# CubeX2000.net
KiCad netlist of a schematic drawn in EAGLE
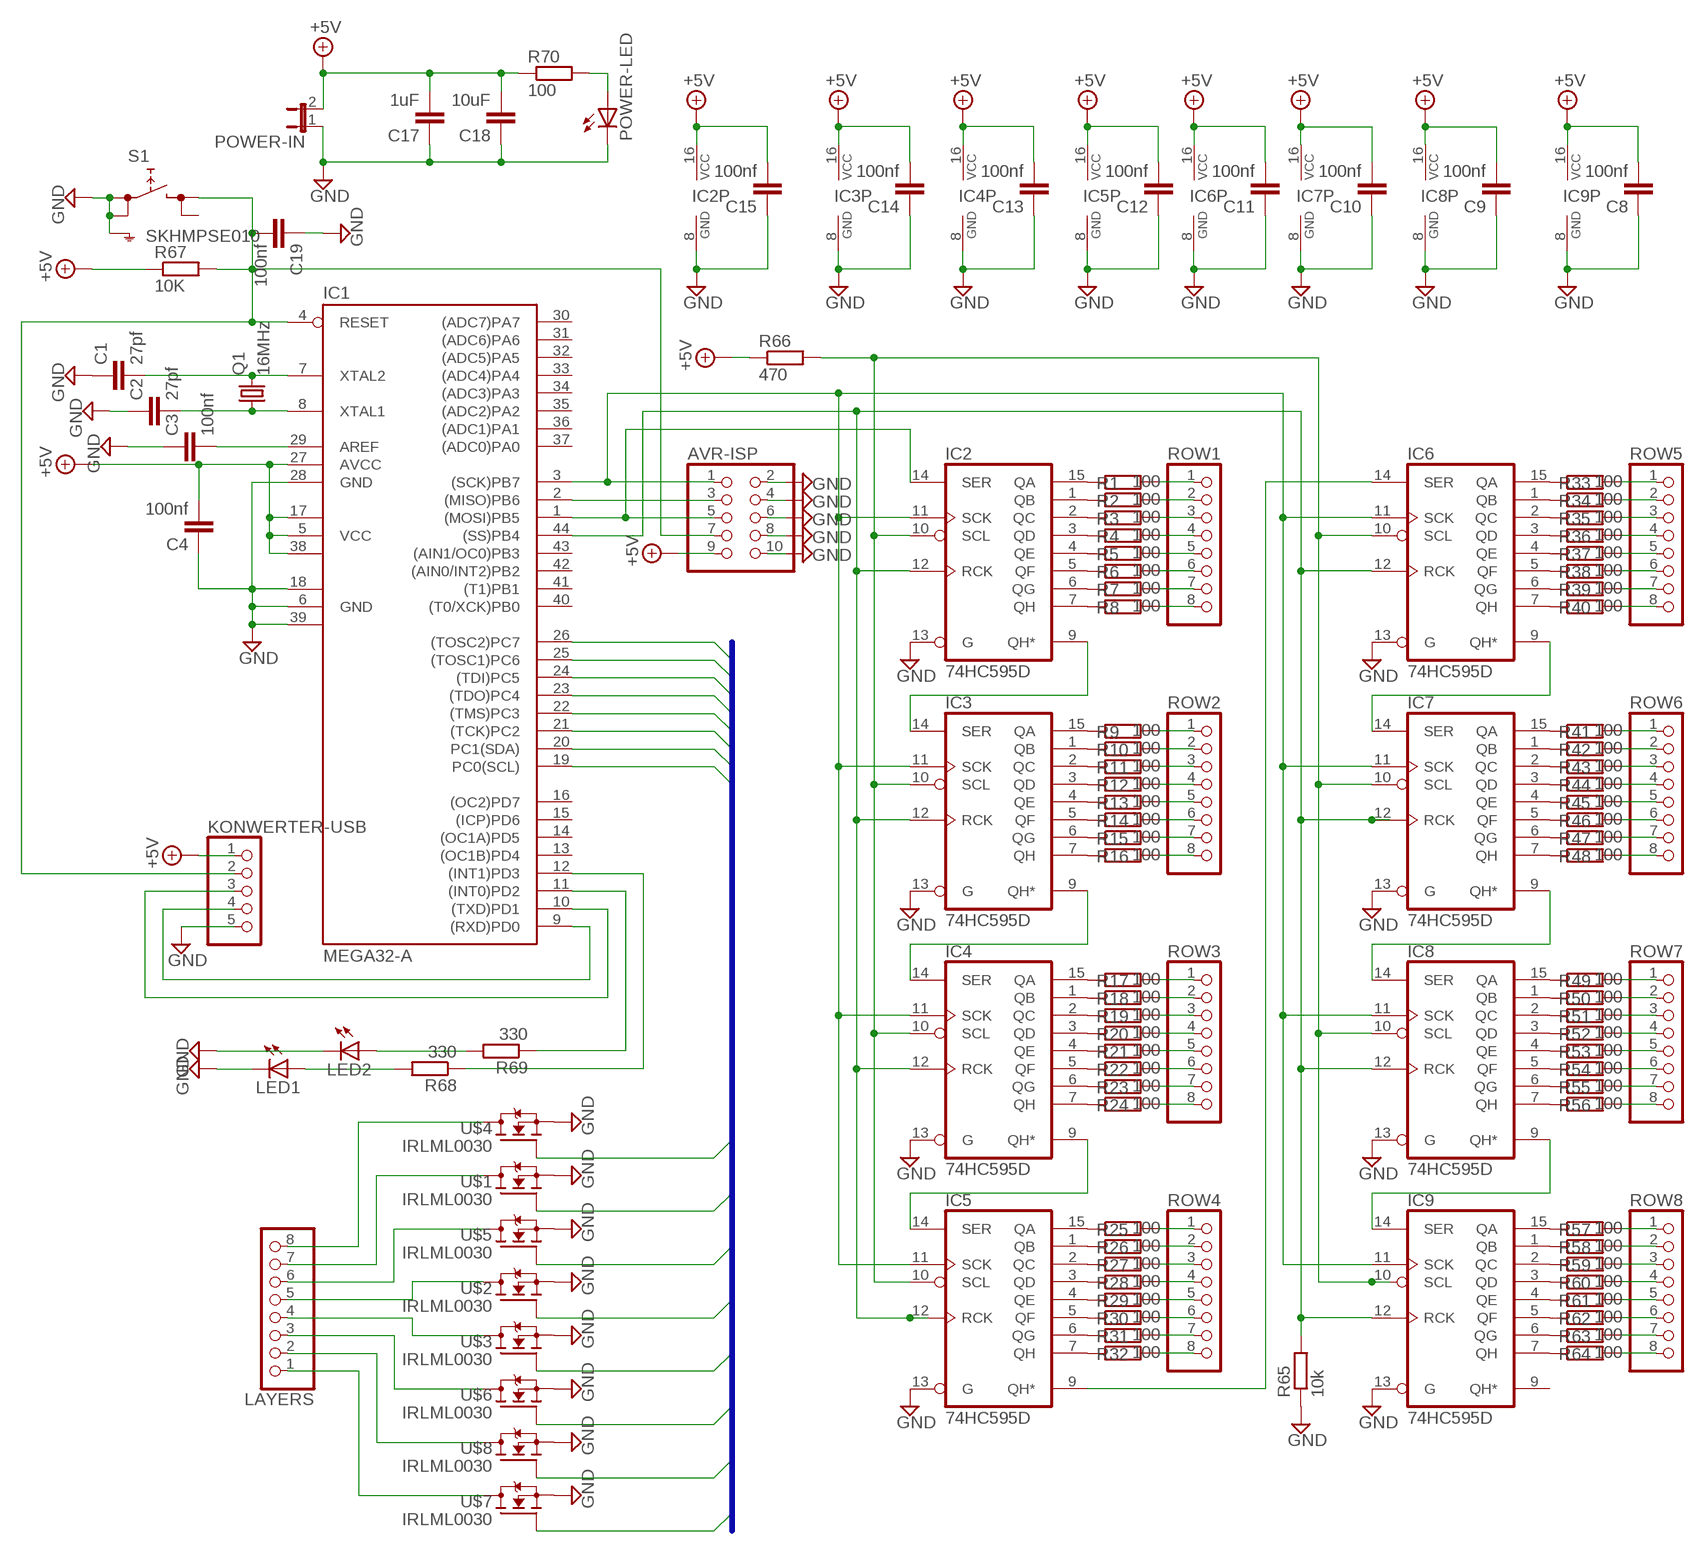
[diagram p0: schematic, sheet 1]

(export (version "E")
  (design (tool "Eeschema 10.0.6"))
  (components
    (comp (ref "AVR-ISP")
      (value "PINHD-2X5")
      (footprint "eagle-import:2X05")
      (libsource (lib "eagle-import") (part "PINHD-2X5"))
    )
    (comp (ref "C1")
      (value "27pf")
      (footprint "eagle-import:C1206")
      (libsource (lib "eagle-import") (part "C-EUC1206"))
    )
    (comp (ref "C2")
      (value "27pf")
      (footprint "eagle-import:C1206")
      (libsource (lib "eagle-import") (part "C-EUC1206"))
    )
    (comp (ref "C3")
      (value "100nf")
      (footprint "eagle-import:C1206")
      (libsource (lib "eagle-import") (part "C-EUC1206"))
    )
    (comp (ref "C4")
      (value "100nf")
      (footprint "eagle-import:C1206")
      (libsource (lib "eagle-import") (part "C-EUC1206"))
    )
    (comp (ref "C8")
      (value "100nf")
      (footprint "eagle-import:C1206")
      (libsource (lib "eagle-import") (part "C-EUC1206"))
    )
    (comp (ref "C9")
      (value "100nf")
      (footprint "eagle-import:C1206")
      (libsource (lib "eagle-import") (part "C-EUC1206"))
    )
    (comp (ref "C10")
      (value "100nf")
      (footprint "eagle-import:C1206")
      (libsource (lib "eagle-import") (part "C-EUC1206"))
    )
    (comp (ref "C11")
      (value "100nf")
      (footprint "eagle-import:C1206")
      (libsource (lib "eagle-import") (part "C-EUC1206"))
    )
    (comp (ref "C12")
      (value "100nf")
      (footprint "eagle-import:C1206")
      (libsource (lib "eagle-import") (part "C-EUC1206"))
    )
    (comp (ref "C13")
      (value "100nf")
      (footprint "eagle-import:C1206")
      (libsource (lib "eagle-import") (part "C-EUC1206"))
    )
    (comp (ref "C14")
      (value "100nf")
      (footprint "eagle-import:C1206")
      (libsource (lib "eagle-import") (part "C-EUC1206"))
    )
    (comp (ref "C15")
      (value "100nf")
      (footprint "eagle-import:C1206")
      (libsource (lib "eagle-import") (part "C-EUC1206"))
    )
    (comp (ref "C17")
      (value "1uF")
      (footprint "eagle-import:C1206")
      (libsource (lib "eagle-import") (part "C-EUC1206"))
    )
    (comp (ref "C18")
      (value "10uF")
      (footprint "eagle-import:C1206")
      (libsource (lib "eagle-import") (part "C-EUC1206"))
    )
    (comp (ref "C19")
      (value "100nf")
      (footprint "eagle-import:C1206")
      (libsource (lib "eagle-import") (part "C-EUC1206"))
    )
    (comp (ref "IC1")
      (value "MEGA32-A")
      (footprint "eagle-import:TQFP44")
      (fields (field (name "MPN") "ATMEGA32-16AU"))
      (libsource (lib "eagle-import") (part "MEGA32-A"))
    )
    (comp (ref "IC2")
      (value "74HC595D")
      (footprint "eagle-import:SO16")
      (libsource (lib "eagle-import") (part "74595DHC"))
    )
    (comp (ref "IC3")
      (value "74HC595D")
      (footprint "eagle-import:SO16")
      (libsource (lib "eagle-import") (part "74595DHC"))
    )
    (comp (ref "IC4")
      (value "74HC595D")
      (footprint "eagle-import:SO16")
      (libsource (lib "eagle-import") (part "74595DHC"))
    )
    (comp (ref "IC5")
      (value "74HC595D")
      (footprint "eagle-import:SO16")
      (libsource (lib "eagle-import") (part "74595DHC"))
    )
    (comp (ref "IC6")
      (value "74HC595D")
      (footprint "eagle-import:SO16")
      (libsource (lib "eagle-import") (part "74595DHC"))
    )
    (comp (ref "IC7")
      (value "74HC595D")
      (footprint "eagle-import:SO16")
      (libsource (lib "eagle-import") (part "74595DHC"))
    )
    (comp (ref "IC8")
      (value "74HC595D")
      (footprint "eagle-import:SO16")
      (libsource (lib "eagle-import") (part "74595DHC"))
    )
    (comp (ref "IC9")
      (value "74HC595D")
      (footprint "eagle-import:SO16")
      (libsource (lib "eagle-import") (part "74595DHC"))
    )
    (comp (ref "KONWERTER-USB")
      (value "PINHD-1X5")
      (footprint "eagle-import:1X05")
      (libsource (lib "eagle-import") (part "PINHD-1X5"))
    )
    (comp (ref "LAYERS")
      (value "PINHD-1X8")
      (footprint "eagle-import:1X08")
      (libsource (lib "eagle-import") (part "PINHD-1X8"))
    )
    (comp (ref "LED1")
      (value "LEDSMT1206")
      (footprint "eagle-import:1206")
      (libsource (lib "eagle-import") (part "LEDSMT1206"))
    )
    (comp (ref "LED2")
      (value "LEDSMT1206")
      (footprint "eagle-import:1206")
      (libsource (lib "eagle-import") (part "LEDSMT1206"))
    )
    (comp (ref "POWER-IN")
      (value "JP1E")
      (footprint "eagle-import:JP1")
      (libsource (lib "eagle-import") (part "JP1E"))
    )
    (comp (ref "POWER-LED")
      (value "LEDSMT1206")
      (footprint "eagle-import:1206")
      (libsource (lib "eagle-import") (part "LEDSMT1206"))
    )
    (comp (ref "Q1")
      (value "16MHz")
      (footprint "eagle-import:HC49_S")
      (libsource (lib "eagle-import") (part "CRYSTALHC49S"))
    )
    (comp (ref "R1")
      (value "100")
      (footprint "eagle-import:R1206")
      (libsource (lib "eagle-import") (part "R-EU_R1206"))
    )
    (comp (ref "R2")
      (value "100")
      (footprint "eagle-import:R1206")
      (libsource (lib "eagle-import") (part "R-EU_R1206"))
    )
    (comp (ref "R3")
      (value "100")
      (footprint "eagle-import:R1206")
      (libsource (lib "eagle-import") (part "R-EU_R1206"))
    )
    (comp (ref "R4")
      (value "100")
      (footprint "eagle-import:R1206")
      (libsource (lib "eagle-import") (part "R-EU_R1206"))
    )
    (comp (ref "R5")
      (value "100")
      (footprint "eagle-import:R1206")
      (libsource (lib "eagle-import") (part "R-EU_R1206"))
    )
    (comp (ref "R6")
      (value "100")
      (footprint "eagle-import:R1206")
      (libsource (lib "eagle-import") (part "R-EU_R1206"))
    )
    (comp (ref "R7")
      (value "100")
      (footprint "eagle-import:R1206")
      (libsource (lib "eagle-import") (part "R-EU_R1206"))
    )
    (comp (ref "R8")
      (value "100")
      (footprint "eagle-import:R1206")
      (libsource (lib "eagle-import") (part "R-EU_R1206"))
    )
    (comp (ref "R9")
      (value "100")
      (footprint "eagle-import:R1206")
      (libsource (lib "eagle-import") (part "R-EU_R1206"))
    )
    (comp (ref "R10")
      (value "100")
      (footprint "eagle-import:R1206")
      (libsource (lib "eagle-import") (part "R-EU_R1206"))
    )
    (comp (ref "R11")
      (value "100")
      (footprint "eagle-import:R1206")
      (libsource (lib "eagle-import") (part "R-EU_R1206"))
    )
    (comp (ref "R12")
      (value "100")
      (footprint "eagle-import:R1206")
      (libsource (lib "eagle-import") (part "R-EU_R1206"))
    )
    (comp (ref "R13")
      (value "100")
      (footprint "eagle-import:R1206")
      (libsource (lib "eagle-import") (part "R-EU_R1206"))
    )
    (comp (ref "R14")
      (value "100")
      (footprint "eagle-import:R1206")
      (libsource (lib "eagle-import") (part "R-EU_R1206"))
    )
    (comp (ref "R15")
      (value "100")
      (footprint "eagle-import:R1206")
      (libsource (lib "eagle-import") (part "R-EU_R1206"))
    )
    (comp (ref "R16")
      (value "100")
      (footprint "eagle-import:R1206")
      (libsource (lib "eagle-import") (part "R-EU_R1206"))
    )
    (comp (ref "R17")
      (value "100")
      (footprint "eagle-import:R1206")
      (libsource (lib "eagle-import") (part "R-EU_R1206"))
    )
    (comp (ref "R18")
      (value "100")
      (footprint "eagle-import:R1206")
      (libsource (lib "eagle-import") (part "R-EU_R1206"))
    )
    (comp (ref "R19")
      (value "100")
      (footprint "eagle-import:R1206")
      (libsource (lib "eagle-import") (part "R-EU_R1206"))
    )
    (comp (ref "R20")
      (value "100")
      (footprint "eagle-import:R1206")
      (libsource (lib "eagle-import") (part "R-EU_R1206"))
    )
    (comp (ref "R21")
      (value "100")
      (footprint "eagle-import:R1206")
      (libsource (lib "eagle-import") (part "R-EU_R1206"))
    )
    (comp (ref "R22")
      (value "100")
      (footprint "eagle-import:R1206")
      (libsource (lib "eagle-import") (part "R-EU_R1206"))
    )
    (comp (ref "R23")
      (value "100")
      (footprint "eagle-import:R1206")
      (libsource (lib "eagle-import") (part "R-EU_R1206"))
    )
    (comp (ref "R24")
      (value "100")
      (footprint "eagle-import:R1206")
      (libsource (lib "eagle-import") (part "R-EU_R1206"))
    )
    (comp (ref "R25")
      (value "100")
      (footprint "eagle-import:R1206")
      (libsource (lib "eagle-import") (part "R-EU_R1206"))
    )
    (comp (ref "R26")
      (value "100")
      (footprint "eagle-import:R1206")
      (libsource (lib "eagle-import") (part "R-EU_R1206"))
    )
    (comp (ref "R27")
      (value "100")
      (footprint "eagle-import:R1206")
      (libsource (lib "eagle-import") (part "R-EU_R1206"))
    )
    (comp (ref "R28")
      (value "100")
      (footprint "eagle-import:R1206")
      (libsource (lib "eagle-import") (part "R-EU_R1206"))
    )
    (comp (ref "R29")
      (value "100")
      (footprint "eagle-import:R1206")
      (libsource (lib "eagle-import") (part "R-EU_R1206"))
    )
    (comp (ref "R30")
      (value "100")
      (footprint "eagle-import:R1206")
      (libsource (lib "eagle-import") (part "R-EU_R1206"))
    )
    (comp (ref "R31")
      (value "100")
      (footprint "eagle-import:R1206")
      (libsource (lib "eagle-import") (part "R-EU_R1206"))
    )
    (comp (ref "R32")
      (value "100")
      (footprint "eagle-import:R1206")
      (libsource (lib "eagle-import") (part "R-EU_R1206"))
    )
    (comp (ref "R33")
      (value "100")
      (footprint "eagle-import:R1206")
      (libsource (lib "eagle-import") (part "R-EU_R1206"))
    )
    (comp (ref "R34")
      (value "100")
      (footprint "eagle-import:R1206")
      (libsource (lib "eagle-import") (part "R-EU_R1206"))
    )
    (comp (ref "R35")
      (value "100")
      (footprint "eagle-import:R1206")
      (libsource (lib "eagle-import") (part "R-EU_R1206"))
    )
    (comp (ref "R36")
      (value "100")
      (footprint "eagle-import:R1206")
      (libsource (lib "eagle-import") (part "R-EU_R1206"))
    )
    (comp (ref "R37")
      (value "100")
      (footprint "eagle-import:R1206")
      (libsource (lib "eagle-import") (part "R-EU_R1206"))
    )
    (comp (ref "R38")
      (value "100")
      (footprint "eagle-import:R1206")
      (libsource (lib "eagle-import") (part "R-EU_R1206"))
    )
    (comp (ref "R39")
      (value "100")
      (footprint "eagle-import:R1206")
      (libsource (lib "eagle-import") (part "R-EU_R1206"))
    )
    (comp (ref "R40")
      (value "100")
      (footprint "eagle-import:R1206")
      (libsource (lib "eagle-import") (part "R-EU_R1206"))
    )
    (comp (ref "R41")
      (value "100")
      (footprint "eagle-import:R1206")
      (libsource (lib "eagle-import") (part "R-EU_R1206"))
    )
    (comp (ref "R42")
      (value "100")
      (footprint "eagle-import:R1206")
      (libsource (lib "eagle-import") (part "R-EU_R1206"))
    )
    (comp (ref "R43")
      (value "100")
      (footprint "eagle-import:R1206")
      (libsource (lib "eagle-import") (part "R-EU_R1206"))
    )
    (comp (ref "R44")
      (value "100")
      (footprint "eagle-import:R1206")
      (libsource (lib "eagle-import") (part "R-EU_R1206"))
    )
    (comp (ref "R45")
      (value "100")
      (footprint "eagle-import:R1206")
      (libsource (lib "eagle-import") (part "R-EU_R1206"))
    )
    (comp (ref "R46")
      (value "100")
      (footprint "eagle-import:R1206")
      (libsource (lib "eagle-import") (part "R-EU_R1206"))
    )
    (comp (ref "R47")
      (value "100")
      (footprint "eagle-import:R1206")
      (libsource (lib "eagle-import") (part "R-EU_R1206"))
    )
    (comp (ref "R48")
      (value "100")
      (footprint "eagle-import:R1206")
      (libsource (lib "eagle-import") (part "R-EU_R1206"))
    )
    (comp (ref "R49")
      (value "100")
      (footprint "eagle-import:R1206")
      (libsource (lib "eagle-import") (part "R-EU_R1206"))
    )
    (comp (ref "R50")
      (value "100")
      (footprint "eagle-import:R1206")
      (libsource (lib "eagle-import") (part "R-EU_R1206"))
    )
    (comp (ref "R51")
      (value "100")
      (footprint "eagle-import:R1206")
      (libsource (lib "eagle-import") (part "R-EU_R1206"))
    )
    (comp (ref "R52")
      (value "100")
      (footprint "eagle-import:R1206")
      (libsource (lib "eagle-import") (part "R-EU_R1206"))
    )
    (comp (ref "R53")
      (value "100")
      (footprint "eagle-import:R1206")
      (libsource (lib "eagle-import") (part "R-EU_R1206"))
    )
    (comp (ref "R54")
      (value "100")
      (footprint "eagle-import:R1206")
      (libsource (lib "eagle-import") (part "R-EU_R1206"))
    )
    (comp (ref "R55")
      (value "100")
      (footprint "eagle-import:R1206")
      (libsource (lib "eagle-import") (part "R-EU_R1206"))
    )
    (comp (ref "R56")
      (value "100")
      (footprint "eagle-import:R1206")
      (libsource (lib "eagle-import") (part "R-EU_R1206"))
    )
    (comp (ref "R57")
      (value "100")
      (footprint "eagle-import:R1206")
      (libsource (lib "eagle-import") (part "R-EU_R1206"))
    )
    (comp (ref "R58")
      (value "100")
      (footprint "eagle-import:R1206")
      (libsource (lib "eagle-import") (part "R-EU_R1206"))
    )
    (comp (ref "R59")
      (value "100")
      (footprint "eagle-import:R1206")
      (libsource (lib "eagle-import") (part "R-EU_R1206"))
    )
    (comp (ref "R60")
      (value "100")
      (footprint "eagle-import:R1206")
      (libsource (lib "eagle-import") (part "R-EU_R1206"))
    )
    (comp (ref "R61")
      (value "100")
      (footprint "eagle-import:R1206")
      (libsource (lib "eagle-import") (part "R-EU_R1206"))
    )
    (comp (ref "R62")
      (value "100")
      (footprint "eagle-import:R1206")
      (libsource (lib "eagle-import") (part "R-EU_R1206"))
    )
    (comp (ref "R63")
      (value "100")
      (footprint "eagle-import:R1206")
      (libsource (lib "eagle-import") (part "R-EU_R1206"))
    )
    (comp (ref "R64")
      (value "100")
      (footprint "eagle-import:R1206")
      (libsource (lib "eagle-import") (part "R-EU_R1206"))
    )
    (comp (ref "R65")
      (value "10k")
      (footprint "eagle-import:R1206")
      (libsource (lib "eagle-import") (part "R-EU_R1206"))
    )
    (comp (ref "R66")
      (value "470")
      (footprint "eagle-import:R1206")
      (libsource (lib "eagle-import") (part "R-EU_R1206"))
    )
    (comp (ref "R67")
      (value "10K")
      (footprint "eagle-import:R1206")
      (libsource (lib "eagle-import") (part "R-EU_R1206"))
    )
    (comp (ref "R68")
      (value "330")
      (footprint "eagle-import:R1206")
      (libsource (lib "eagle-import") (part "R-EU_R1206"))
    )
    (comp (ref "R69")
      (value "330")
      (footprint "eagle-import:R1206")
      (libsource (lib "eagle-import") (part "R-EU_R1206"))
    )
    (comp (ref "R70")
      (value "100")
      (footprint "eagle-import:R1206")
      (libsource (lib "eagle-import") (part "R-EU_R1206"))
    )
    (comp (ref "ROW1")
      (value "PINHD-1X8")
      (footprint "eagle-import:1X08")
      (libsource (lib "eagle-import") (part "PINHD-1X8"))
    )
    (comp (ref "ROW2")
      (value "PINHD-1X8")
      (footprint "eagle-import:1X08")
      (libsource (lib "eagle-import") (part "PINHD-1X8"))
    )
    (comp (ref "ROW3")
      (value "PINHD-1X8")
      (footprint "eagle-import:1X08")
      (libsource (lib "eagle-import") (part "PINHD-1X8"))
    )
    (comp (ref "ROW4")
      (value "PINHD-1X8")
      (footprint "eagle-import:1X08")
      (libsource (lib "eagle-import") (part "PINHD-1X8"))
    )
    (comp (ref "ROW5")
      (value "PINHD-1X8")
      (footprint "eagle-import:1X08")
      (libsource (lib "eagle-import") (part "PINHD-1X8"))
    )
    (comp (ref "ROW6")
      (value "PINHD-1X8")
      (footprint "eagle-import:1X08")
      (libsource (lib "eagle-import") (part "PINHD-1X8"))
    )
    (comp (ref "ROW7")
      (value "PINHD-1X8")
      (footprint "eagle-import:1X08")
      (libsource (lib "eagle-import") (part "PINHD-1X8"))
    )
    (comp (ref "ROW8")
      (value "PINHD-1X8")
      (footprint "eagle-import:1X08")
      (libsource (lib "eagle-import") (part "PINHD-1X8"))
    )
    (comp (ref "S1")
      (value "SKHMPSE010")
      (footprint "eagle-import:SKHMPXE010")
      (libsource (lib "eagle-import") (part "SKHMPE010S"))
    )
    (comp (ref "U$1")
      (value "IRLML0030")
      (footprint "eagle-import:SOT23")
      (libsource (lib "eagle-import") (part "IRLML0030"))
    )
    (comp (ref "U$2")
      (value "IRLML0030")
      (footprint "eagle-import:SOT23")
      (libsource (lib "eagle-import") (part "IRLML0030"))
    )
    (comp (ref "U$3")
      (value "IRLML0030")
      (footprint "eagle-import:SOT23")
      (libsource (lib "eagle-import") (part "IRLML0030"))
    )
    (comp (ref "U$4")
      (value "IRLML0030")
      (footprint "eagle-import:SOT23")
      (libsource (lib "eagle-import") (part "IRLML0030"))
    )
    (comp (ref "U$5")
      (value "IRLML0030")
      (footprint "eagle-import:SOT23")
      (libsource (lib "eagle-import") (part "IRLML0030"))
    )
    (comp (ref "U$6")
      (value "IRLML0030")
      (footprint "eagle-import:SOT23")
      (libsource (lib "eagle-import") (part "IRLML0030"))
    )
    (comp (ref "U$7")
      (value "IRLML0030")
      (footprint "eagle-import:SOT23")
      (libsource (lib "eagle-import") (part "IRLML0030"))
    )
    (comp (ref "U$8")
      (value "IRLML0030")
      (footprint "eagle-import:SOT23")
      (libsource (lib "eagle-import") (part "IRLML0030"))
    )
  )
  (nets
    (net (code "1") (name "+5V") (class "Default")
      (node (ref "AVR-ISP") (pin "9") (pinfunction "9_9") (pintype "passive"))
      (node (ref "C10") (pin "2") (pinfunction "2_2") (pintype "passive"))
      (node (ref "C11") (pin "2") (pinfunction "2_2") (pintype "passive"))
      (node (ref "C12") (pin "2") (pinfunction "2_2") (pintype "passive"))
      (node (ref "C13") (pin "2") (pinfunction "2_2") (pintype "passive"))
      (node (ref "C14") (pin "2") (pinfunction "2_2") (pintype "passive"))
      (node (ref "C15") (pin "2") (pinfunction "2_2") (pintype "passive"))
      (node (ref "C17") (pin "2") (pinfunction "2_2") (pintype "passive"))
      (node (ref "C18") (pin "2") (pinfunction "2_2") (pintype "passive"))
      (node (ref "C4") (pin "2") (pinfunction "2_2") (pintype "passive"))
      (node (ref "C8") (pin "2") (pinfunction "2_2") (pintype "passive"))
      (node (ref "C9") (pin "2") (pinfunction "2_2") (pintype "passive"))
      (node (ref "IC1") (pin "17") (pinfunction "VCC1_17") (pintype "power_in"))
      (node (ref "IC1") (pin "27") (pinfunction "AVCC_27") (pintype "power_in"))
      (node (ref "IC1") (pin "38") (pinfunction "VCC2_38") (pintype "power_in"))
      (node (ref "IC1") (pin "5") (pinfunction "VCC_5") (pintype "power_in"))
      (node (ref "IC2") (pin "16") (pinfunction "VCC_16") (pintype "power_in"))
      (node (ref "IC3") (pin "16") (pinfunction "VCC_16") (pintype "power_in"))
      (node (ref "IC4") (pin "16") (pinfunction "VCC_16") (pintype "power_in"))
      (node (ref "IC5") (pin "16") (pinfunction "VCC_16") (pintype "power_in"))
      (node (ref "IC6") (pin "16") (pinfunction "VCC_16") (pintype "power_in"))
      (node (ref "IC7") (pin "16") (pinfunction "VCC_16") (pintype "power_in"))
      (node (ref "IC8") (pin "16") (pinfunction "VCC_16") (pintype "power_in"))
      (node (ref "IC9") (pin "16") (pinfunction "VCC_16") (pintype "power_in"))
      (node (ref "KONWERTER-USB") (pin "1") (pinfunction "1_1") (pintype "passive"))
      (node (ref "POWER-IN") (pin "2") (pinfunction "2_2") (pintype "passive"))
      (node (ref "R66") (pin "1") (pinfunction "1_1") (pintype "passive"))
      (node (ref "R67") (pin "1") (pinfunction "1_1") (pintype "passive"))
      (node (ref "R70") (pin "1") (pinfunction "1_1") (pintype "passive"))
    )
    (net (code "2") (name "/LAYERS1") (class "Default")
      (node (ref "IC1") (pin "19") (pinfunction "PC0(SCL)_19") (pintype "bidirectional"))
      (node (ref "U$7") (pin "1") (pinfunction "G_1") (pintype "passive"))
    )
    (net (code "3") (name "/LAYERS2") (class "Default")
      (node (ref "IC1") (pin "20") (pinfunction "PC1(SDA)_20") (pintype "bidirectional"))
      (node (ref "U$8") (pin "1") (pinfunction "G_1") (pintype "passive"))
    )
    (net (code "4") (name "/LAYERS3") (class "Default")
      (node (ref "IC1") (pin "21") (pinfunction "(TCK)PC2_21") (pintype "bidirectional"))
      (node (ref "U$6") (pin "1") (pinfunction "G_1") (pintype "passive"))
    )
    (net (code "5") (name "/LAYERS4") (class "Default")
      (node (ref "IC1") (pin "22") (pinfunction "(TMS)PC3_22") (pintype "bidirectional"))
      (node (ref "U$3") (pin "1") (pinfunction "G_1") (pintype "passive"))
    )
    (net (code "6") (name "/LAYERS5") (class "Default")
      (node (ref "IC1") (pin "23") (pinfunction "(TDO)PC4_23") (pintype "bidirectional"))
      (node (ref "U$2") (pin "1") (pinfunction "G_1") (pintype "passive"))
    )
    (net (code "7") (name "/LAYERS6") (class "Default")
      (node (ref "IC1") (pin "24") (pinfunction "(TDI)PC5_24") (pintype "bidirectional"))
      (node (ref "U$5") (pin "1") (pinfunction "G_1") (pintype "passive"))
    )
    (net (code "8") (name "/LAYERS7") (class "Default")
      (node (ref "IC1") (pin "25") (pinfunction "(TOSC1)PC6_25") (pintype "bidirectional"))
      (node (ref "U$1") (pin "1") (pinfunction "G_1") (pintype "passive"))
    )
    (net (code "9") (name "/LAYERS8") (class "Default")
      (node (ref "IC1") (pin "26") (pinfunction "(TOSC2)PC7_26") (pintype "bidirectional"))
      (node (ref "U$4") (pin "1") (pinfunction "G_1") (pintype "passive"))
    )
    (net (code "10") (name "GND") (class "Default")
      (node (ref "AVR-ISP") (pin "10") (pinfunction "10_10") (pintype "passive"))
      (node (ref "AVR-ISP") (pin "2") (pinfunction "2_2") (pintype "passive"))
      (node (ref "AVR-ISP") (pin "4") (pinfunction "4_4") (pintype "passive"))
      (node (ref "AVR-ISP") (pin "6") (pinfunction "6_6") (pintype "passive"))
      (node (ref "AVR-ISP") (pin "8") (pinfunction "8_8") (pintype "passive"))
      (node (ref "C1") (pin "1") (pinfunction "1_1") (pintype "passive"))
      (node (ref "C10") (pin "1") (pinfunction "1_1") (pintype "passive"))
      (node (ref "C11") (pin "1") (pinfunction "1_1") (pintype "passive"))
      (node (ref "C12") (pin "1") (pinfunction "1_1") (pintype "passive"))
      (node (ref "C13") (pin "1") (pinfunction "1_1") (pintype "passive"))
      (node (ref "C14") (pin "1") (pinfunction "1_1") (pintype "passive"))
      (node (ref "C15") (pin "1") (pinfunction "1_1") (pintype "passive"))
      (node (ref "C17") (pin "1") (pinfunction "1_1") (pintype "passive"))
      (node (ref "C18") (pin "1") (pinfunction "1_1") (pintype "passive"))
      (node (ref "C19") (pin "1") (pinfunction "1_1") (pintype "passive"))
      (node (ref "C2") (pin "1") (pinfunction "1_1") (pintype "passive"))
      (node (ref "C3") (pin "1") (pinfunction "1_1") (pintype "passive"))
      (node (ref "C4") (pin "1") (pinfunction "1_1") (pintype "passive"))
      (node (ref "C8") (pin "1") (pinfunction "1_1") (pintype "passive"))
      (node (ref "C9") (pin "1") (pinfunction "1_1") (pintype "passive"))
      (node (ref "IC1") (pin "18") (pinfunction "GND1_18") (pintype "power_in"))
      (node (ref "IC1") (pin "28") (pinfunction "GND_28") (pintype "power_in"))
      (node (ref "IC1") (pin "39") (pinfunction "GND2_39") (pintype "power_in"))
      (node (ref "IC1") (pin "6") (pinfunction "GND_6") (pintype "power_in"))
      (node (ref "IC2") (pin "13") (pinfunction "G_13") (pintype "input"))
      (node (ref "IC2") (pin "8") (pinfunction "GND_8") (pintype "power_in"))
      (node (ref "IC3") (pin "13") (pinfunction "G_13") (pintype "input"))
      (node (ref "IC3") (pin "8") (pinfunction "GND_8") (pintype "power_in"))
      (node (ref "IC4") (pin "13") (pinfunction "G_13") (pintype "input"))
      (node (ref "IC4") (pin "8") (pinfunction "GND_8") (pintype "power_in"))
      (node (ref "IC5") (pin "13") (pinfunction "G_13") (pintype "input"))
      (node (ref "IC5") (pin "8") (pinfunction "GND_8") (pintype "power_in"))
      (node (ref "IC6") (pin "13") (pinfunction "G_13") (pintype "input"))
      (node (ref "IC6") (pin "8") (pinfunction "GND_8") (pintype "power_in"))
      (node (ref "IC7") (pin "13") (pinfunction "G_13") (pintype "input"))
      (node (ref "IC7") (pin "8") (pinfunction "GND_8") (pintype "power_in"))
      (node (ref "IC8") (pin "13") (pinfunction "G_13") (pintype "input"))
      (node (ref "IC8") (pin "8") (pinfunction "GND_8") (pintype "power_in"))
      (node (ref "IC9") (pin "13") (pinfunction "G_13") (pintype "input"))
      (node (ref "IC9") (pin "8") (pinfunction "GND_8") (pintype "power_in"))
      (node (ref "KONWERTER-USB") (pin "5") (pinfunction "5_5") (pintype "passive"))
      (node (ref "LED1") (pin "C") (pinfunction "C_C") (pintype "passive"))
      (node (ref "LED2") (pin "C") (pinfunction "C_C") (pintype "passive"))
      (node (ref "POWER-IN") (pin "1") (pinfunction "1_1") (pintype "passive"))
      (node (ref "POWER-LED") (pin "C") (pinfunction "C_C") (pintype "passive"))
      (node (ref "R65") (pin "1") (pinfunction "1_1") (pintype "passive"))
      (node (ref "S1") (pin "1") (pinfunction "1.1_1") (pintype "passive"))
      (node (ref "S1") (pin "2") (pinfunction "1.2_2") (pintype "passive"))
      (node (ref "S1") (pin "5") (pinfunction "SH_5") (pintype "passive"))
      (node (ref "U$1") (pin "2") (pinfunction "S_2") (pintype "passive"))
      (node (ref "U$2") (pin "2") (pinfunction "S_2") (pintype "passive"))
      (node (ref "U$3") (pin "2") (pinfunction "S_2") (pintype "passive"))
      (node (ref "U$4") (pin "2") (pinfunction "S_2") (pintype "passive"))
      (node (ref "U$5") (pin "2") (pinfunction "S_2") (pintype "passive"))
      (node (ref "U$6") (pin "2") (pinfunction "S_2") (pintype "passive"))
      (node (ref "U$7") (pin "2") (pinfunction "S_2") (pintype "passive"))
      (node (ref "U$8") (pin "2") (pinfunction "S_2") (pintype "passive"))
    )
    (net (code "11") (name "Net-(IC1-(INT0)PD2)") (class "Default")
      (node (ref "IC1") (pin "11") (pinfunction "(INT0)PD2_11") (pintype "bidirectional"))
      (node (ref "R69") (pin "1") (pinfunction "1_1") (pintype "passive"))
    )
    (net (code "12") (name "Net-(IC1-(INT1)PD3)") (class "Default")
      (node (ref "IC1") (pin "12") (pinfunction "(INT1)PD3_12") (pintype "bidirectional"))
      (node (ref "R68") (pin "1") (pinfunction "1_1") (pintype "passive"))
    )
    (net (code "13") (name "Net-(IC1-(MISO)PB6)") (class "Default")
      (node (ref "AVR-ISP") (pin "3") (pinfunction "3_3") (pintype "passive"))
      (node (ref "IC1") (pin "2") (pinfunction "(MISO)PB6_2") (pintype "bidirectional"))
    )
    (net (code "14") (name "Net-(IC1-(MOSI)PB5)") (class "Default")
      (node (ref "AVR-ISP") (pin "5") (pinfunction "5_5") (pintype "passive"))
      (node (ref "IC1") (pin "1") (pinfunction "(MOSI)PB5_1") (pintype "bidirectional"))
      (node (ref "IC2") (pin "14") (pinfunction "SER_14") (pintype "input"))
    )
    (net (code "15") (name "Net-(IC1-(RXD)PD0)") (class "Default")
      (node (ref "IC1") (pin "9") (pinfunction "(RXD)PD0_9") (pintype "bidirectional"))
      (node (ref "KONWERTER-USB") (pin "4") (pinfunction "4_4") (pintype "passive"))
    )
    (net (code "16") (name "Net-(IC1-(SCK)PB7)") (class "Default")
      (node (ref "AVR-ISP") (pin "1") (pinfunction "1_1") (pintype "passive"))
      (node (ref "IC1") (pin "3") (pinfunction "(SCK)PB7_3") (pintype "bidirectional"))
      (node (ref "IC2") (pin "11") (pinfunction "SCK_11") (pintype "input"))
      (node (ref "IC3") (pin "11") (pinfunction "SCK_11") (pintype "input"))
      (node (ref "IC4") (pin "11") (pinfunction "SCK_11") (pintype "input"))
      (node (ref "IC5") (pin "11") (pinfunction "SCK_11") (pintype "input"))
      (node (ref "IC6") (pin "11") (pinfunction "SCK_11") (pintype "input"))
      (node (ref "IC7") (pin "11") (pinfunction "SCK_11") (pintype "input"))
      (node (ref "IC8") (pin "11") (pinfunction "SCK_11") (pintype "input"))
      (node (ref "IC9") (pin "11") (pinfunction "SCK_11") (pintype "input"))
    )
    (net (code "17") (name "Net-(IC1-(SS)PB4)") (class "Default")
      (node (ref "IC1") (pin "44") (pinfunction "(SS)PB4_44") (pintype "bidirectional"))
      (node (ref "IC2") (pin "12") (pinfunction "RCK_12") (pintype "input"))
      (node (ref "IC3") (pin "12") (pinfunction "RCK_12") (pintype "input"))
      (node (ref "IC4") (pin "12") (pinfunction "RCK_12") (pintype "input"))
      (node (ref "IC5") (pin "12") (pinfunction "RCK_12") (pintype "input"))
      (node (ref "IC6") (pin "12") (pinfunction "RCK_12") (pintype "input"))
      (node (ref "IC7") (pin "12") (pinfunction "RCK_12") (pintype "input"))
      (node (ref "IC8") (pin "12") (pinfunction "RCK_12") (pintype "input"))
      (node (ref "IC9") (pin "12") (pinfunction "RCK_12") (pintype "input"))
      (node (ref "R65") (pin "2") (pinfunction "2_2") (pintype "passive"))
    )
    (net (code "18") (name "Net-(IC1-(TXD)PD1)") (class "Default")
      (node (ref "IC1") (pin "10") (pinfunction "(TXD)PD1_10") (pintype "bidirectional"))
      (node (ref "KONWERTER-USB") (pin "3") (pinfunction "3_3") (pintype "passive"))
    )
    (net (code "19") (name "Net-(IC1-AREF)") (class "Default")
      (node (ref "C3") (pin "2") (pinfunction "2_2") (pintype "passive"))
      (node (ref "IC1") (pin "29") (pinfunction "AREF_29") (pintype "passive"))
    )
    (net (code "20") (name "Net-(IC1-RESET)") (class "Default")
      (node (ref "AVR-ISP") (pin "7") (pinfunction "7_7") (pintype "passive"))
      (node (ref "C19") (pin "2") (pinfunction "2_2") (pintype "passive"))
      (node (ref "IC1") (pin "4") (pinfunction "RESET_4") (pintype "input"))
      (node (ref "KONWERTER-USB") (pin "2") (pinfunction "2_2") (pintype "passive"))
      (node (ref "R67") (pin "2") (pinfunction "2_2") (pintype "passive"))
      (node (ref "S1") (pin "3") (pinfunction "2.1_3") (pintype "passive"))
    )
    (net (code "21") (name "Net-(IC1-XTAL1)") (class "Default")
      (node (ref "C2") (pin "2") (pinfunction "2_2") (pintype "passive"))
      (node (ref "IC1") (pin "8") (pinfunction "XTAL1_8") (pintype "bidirectional"))
      (node (ref "Q1") (pin "1") (pinfunction "1_1") (pintype "passive"))
    )
    (net (code "22") (name "Net-(IC1-XTAL2)") (class "Default")
      (node (ref "C1") (pin "2") (pinfunction "2_2") (pintype "passive"))
      (node (ref "IC1") (pin "7") (pinfunction "XTAL2_7") (pintype "bidirectional"))
      (node (ref "Q1") (pin "2") (pinfunction "2_2") (pintype "passive"))
    )
    (net (code "23") (name "Net-(IC2A-QA)") (class "Default")
      (node (ref "IC2") (pin "15") (pinfunction "QA_15") (pintype "tri_state"))
      (node (ref "R1") (pin "1") (pinfunction "1_1") (pintype "passive"))
    )
    (net (code "24") (name "Net-(IC2A-QB)") (class "Default")
      (node (ref "IC2") (pin "1") (pinfunction "QB_1") (pintype "tri_state"))
      (node (ref "R2") (pin "1") (pinfunction "1_1") (pintype "passive"))
    )
    (net (code "25") (name "Net-(IC2A-QC)") (class "Default")
      (node (ref "IC2") (pin "2") (pinfunction "QC_2") (pintype "tri_state"))
      (node (ref "R3") (pin "1") (pinfunction "1_1") (pintype "passive"))
    )
    (net (code "26") (name "Net-(IC2A-QD)") (class "Default")
      (node (ref "IC2") (pin "3") (pinfunction "QD_3") (pintype "tri_state"))
      (node (ref "R4") (pin "1") (pinfunction "1_1") (pintype "passive"))
    )
    (net (code "27") (name "Net-(IC2A-QE)") (class "Default")
      (node (ref "IC2") (pin "4") (pinfunction "QE_4") (pintype "tri_state"))
      (node (ref "R5") (pin "1") (pinfunction "1_1") (pintype "passive"))
    )
    (net (code "28") (name "Net-(IC2A-QF)") (class "Default")
      (node (ref "IC2") (pin "5") (pinfunction "QF_5") (pintype "tri_state"))
      (node (ref "R6") (pin "1") (pinfunction "1_1") (pintype "passive"))
    )
    (net (code "29") (name "Net-(IC2A-QG)") (class "Default")
      (node (ref "IC2") (pin "6") (pinfunction "QG_6") (pintype "tri_state"))
      (node (ref "R7") (pin "1") (pinfunction "1_1") (pintype "passive"))
    )
    (net (code "30") (name "Net-(IC2A-QH)") (class "Default")
      (node (ref "IC2") (pin "7") (pinfunction "QH_7") (pintype "tri_state"))
      (node (ref "R8") (pin "1") (pinfunction "1_1") (pintype "passive"))
    )
    (net (code "31") (name "Net-(IC2A-QH*)") (class "Default")
      (node (ref "IC2") (pin "9") (pinfunction "QH*_9") (pintype "tri_state"))
      (node (ref "IC3") (pin "14") (pinfunction "SER_14") (pintype "input"))
    )
    (net (code "32") (name "Net-(IC2A-SCL)") (class "Default")
      (node (ref "IC2") (pin "10") (pinfunction "SCL_10") (pintype "input"))
      (node (ref "IC3") (pin "10") (pinfunction "SCL_10") (pintype "input"))
      (node (ref "IC4") (pin "10") (pinfunction "SCL_10") (pintype "input"))
      (node (ref "IC5") (pin "10") (pinfunction "SCL_10") (pintype "input"))
      (node (ref "IC6") (pin "10") (pinfunction "SCL_10") (pintype "input"))
      (node (ref "IC7") (pin "10") (pinfunction "SCL_10") (pintype "input"))
      (node (ref "IC8") (pin "10") (pinfunction "SCL_10") (pintype "input"))
      (node (ref "IC9") (pin "10") (pinfunction "SCL_10") (pintype "input"))
      (node (ref "R66") (pin "2") (pinfunction "2_2") (pintype "passive"))
    )
    (net (code "33") (name "Net-(IC3A-QA)") (class "Default")
      (node (ref "IC3") (pin "15") (pinfunction "QA_15") (pintype "tri_state"))
      (node (ref "R9") (pin "1") (pinfunction "1_1") (pintype "passive"))
    )
    (net (code "34") (name "Net-(IC3A-QB)") (class "Default")
      (node (ref "IC3") (pin "1") (pinfunction "QB_1") (pintype "tri_state"))
      (node (ref "R10") (pin "1") (pinfunction "1_1") (pintype "passive"))
    )
    (net (code "35") (name "Net-(IC3A-QC)") (class "Default")
      (node (ref "IC3") (pin "2") (pinfunction "QC_2") (pintype "tri_state"))
      (node (ref "R11") (pin "1") (pinfunction "1_1") (pintype "passive"))
    )
    (net (code "36") (name "Net-(IC3A-QD)") (class "Default")
      (node (ref "IC3") (pin "3") (pinfunction "QD_3") (pintype "tri_state"))
      (node (ref "R12") (pin "1") (pinfunction "1_1") (pintype "passive"))
    )
    (net (code "37") (name "Net-(IC3A-QE)") (class "Default")
      (node (ref "IC3") (pin "4") (pinfunction "QE_4") (pintype "tri_state"))
      (node (ref "R13") (pin "1") (pinfunction "1_1") (pintype "passive"))
    )
    (net (code "38") (name "Net-(IC3A-QF)") (class "Default")
      (node (ref "IC3") (pin "5") (pinfunction "QF_5") (pintype "tri_state"))
      (node (ref "R14") (pin "1") (pinfunction "1_1") (pintype "passive"))
    )
    (net (code "39") (name "Net-(IC3A-QG)") (class "Default")
      (node (ref "IC3") (pin "6") (pinfunction "QG_6") (pintype "tri_state"))
      (node (ref "R15") (pin "1") (pinfunction "1_1") (pintype "passive"))
    )
    (net (code "40") (name "Net-(IC3A-QH)") (class "Default")
      (node (ref "IC3") (pin "7") (pinfunction "QH_7") (pintype "tri_state"))
      (node (ref "R16") (pin "1") (pinfunction "1_1") (pintype "passive"))
    )
    (net (code "41") (name "Net-(IC3A-QH*)") (class "Default")
      (node (ref "IC3") (pin "9") (pinfunction "QH*_9") (pintype "tri_state"))
      (node (ref "IC4") (pin "14") (pinfunction "SER_14") (pintype "input"))
    )
    (net (code "42") (name "Net-(IC4A-QA)") (class "Default")
      (node (ref "IC4") (pin "15") (pinfunction "QA_15") (pintype "tri_state"))
      (node (ref "R17") (pin "1") (pinfunction "1_1") (pintype "passive"))
    )
    (net (code "43") (name "Net-(IC4A-QB)") (class "Default")
      (node (ref "IC4") (pin "1") (pinfunction "QB_1") (pintype "tri_state"))
      (node (ref "R18") (pin "1") (pinfunction "1_1") (pintype "passive"))
    )
    (net (code "44") (name "Net-(IC4A-QC)") (class "Default")
      (node (ref "IC4") (pin "2") (pinfunction "QC_2") (pintype "tri_state"))
      (node (ref "R19") (pin "1") (pinfunction "1_1") (pintype "passive"))
    )
    (net (code "45") (name "Net-(IC4A-QD)") (class "Default")
      (node (ref "IC4") (pin "3") (pinfunction "QD_3") (pintype "tri_state"))
      (node (ref "R20") (pin "1") (pinfunction "1_1") (pintype "passive"))
    )
    (net (code "46") (name "Net-(IC4A-QE)") (class "Default")
      (node (ref "IC4") (pin "4") (pinfunction "QE_4") (pintype "tri_state"))
      (node (ref "R21") (pin "1") (pinfunction "1_1") (pintype "passive"))
    )
    (net (code "47") (name "Net-(IC4A-QF)") (class "Default")
      (node (ref "IC4") (pin "5") (pinfunction "QF_5") (pintype "tri_state"))
      (node (ref "R22") (pin "1") (pinfunction "1_1") (pintype "passive"))
    )
    (net (code "48") (name "Net-(IC4A-QG)") (class "Default")
      (node (ref "IC4") (pin "6") (pinfunction "QG_6") (pintype "tri_state"))
      (node (ref "R23") (pin "1") (pinfunction "1_1") (pintype "passive"))
    )
    (net (code "49") (name "Net-(IC4A-QH)") (class "Default")
      (node (ref "IC4") (pin "7") (pinfunction "QH_7") (pintype "tri_state"))
      (node (ref "R24") (pin "1") (pinfunction "1_1") (pintype "passive"))
    )
    (net (code "50") (name "Net-(IC4A-QH*)") (class "Default")
      (node (ref "IC4") (pin "9") (pinfunction "QH*_9") (pintype "tri_state"))
      (node (ref "IC5") (pin "14") (pinfunction "SER_14") (pintype "input"))
    )
    (net (code "51") (name "Net-(IC5A-QA)") (class "Default")
      (node (ref "IC5") (pin "15") (pinfunction "QA_15") (pintype "tri_state"))
      (node (ref "R25") (pin "1") (pinfunction "1_1") (pintype "passive"))
    )
    (net (code "52") (name "Net-(IC5A-QB)") (class "Default")
      (node (ref "IC5") (pin "1") (pinfunction "QB_1") (pintype "tri_state"))
      (node (ref "R26") (pin "1") (pinfunction "1_1") (pintype "passive"))
    )
    (net (code "53") (name "Net-(IC5A-QC)") (class "Default")
      (node (ref "IC5") (pin "2") (pinfunction "QC_2") (pintype "tri_state"))
      (node (ref "R27") (pin "1") (pinfunction "1_1") (pintype "passive"))
    )
    (net (code "54") (name "Net-(IC5A-QD)") (class "Default")
      (node (ref "IC5") (pin "3") (pinfunction "QD_3") (pintype "tri_state"))
      (node (ref "R28") (pin "1") (pinfunction "1_1") (pintype "passive"))
    )
    (net (code "55") (name "Net-(IC5A-QE)") (class "Default")
      (node (ref "IC5") (pin "4") (pinfunction "QE_4") (pintype "tri_state"))
      (node (ref "R29") (pin "1") (pinfunction "1_1") (pintype "passive"))
    )
    (net (code "56") (name "Net-(IC5A-QF)") (class "Default")
      (node (ref "IC5") (pin "5") (pinfunction "QF_5") (pintype "tri_state"))
      (node (ref "R30") (pin "1") (pinfunction "1_1") (pintype "passive"))
    )
    (net (code "57") (name "Net-(IC5A-QG)") (class "Default")
      (node (ref "IC5") (pin "6") (pinfunction "QG_6") (pintype "tri_state"))
      (node (ref "R31") (pin "1") (pinfunction "1_1") (pintype "passive"))
    )
    (net (code "58") (name "Net-(IC5A-QH)") (class "Default")
      (node (ref "IC5") (pin "7") (pinfunction "QH_7") (pintype "tri_state"))
      (node (ref "R32") (pin "1") (pinfunction "1_1") (pintype "passive"))
    )
    (net (code "59") (name "Net-(IC5A-QH*)") (class "Default")
      (node (ref "IC5") (pin "9") (pinfunction "QH*_9") (pintype "tri_state"))
      (node (ref "IC6") (pin "14") (pinfunction "SER_14") (pintype "input"))
    )
    (net (code "60") (name "Net-(IC6A-QA)") (class "Default")
      (node (ref "IC6") (pin "15") (pinfunction "QA_15") (pintype "tri_state"))
      (node (ref "R33") (pin "1") (pinfunction "1_1") (pintype "passive"))
    )
    (net (code "61") (name "Net-(IC6A-QB)") (class "Default")
      (node (ref "IC6") (pin "1") (pinfunction "QB_1") (pintype "tri_state"))
      (node (ref "R34") (pin "1") (pinfunction "1_1") (pintype "passive"))
    )
    (net (code "62") (name "Net-(IC6A-QC)") (class "Default")
      (node (ref "IC6") (pin "2") (pinfunction "QC_2") (pintype "tri_state"))
      (node (ref "R35") (pin "1") (pinfunction "1_1") (pintype "passive"))
    )
    (net (code "63") (name "Net-(IC6A-QD)") (class "Default")
      (node (ref "IC6") (pin "3") (pinfunction "QD_3") (pintype "tri_state"))
      (node (ref "R36") (pin "1") (pinfunction "1_1") (pintype "passive"))
    )
    (net (code "64") (name "Net-(IC6A-QE)") (class "Default")
      (node (ref "IC6") (pin "4") (pinfunction "QE_4") (pintype "tri_state"))
      (node (ref "R37") (pin "1") (pinfunction "1_1") (pintype "passive"))
    )
    (net (code "65") (name "Net-(IC6A-QF)") (class "Default")
      (node (ref "IC6") (pin "5") (pinfunction "QF_5") (pintype "tri_state"))
      (node (ref "R38") (pin "1") (pinfunction "1_1") (pintype "passive"))
    )
    (net (code "66") (name "Net-(IC6A-QG)") (class "Default")
      (node (ref "IC6") (pin "6") (pinfunction "QG_6") (pintype "tri_state"))
      (node (ref "R39") (pin "1") (pinfunction "1_1") (pintype "passive"))
    )
    (net (code "67") (name "Net-(IC6A-QH)") (class "Default")
      (node (ref "IC6") (pin "7") (pinfunction "QH_7") (pintype "tri_state"))
      (node (ref "R40") (pin "1") (pinfunction "1_1") (pintype "passive"))
    )
    (net (code "68") (name "Net-(IC6A-QH*)") (class "Default")
      (node (ref "IC6") (pin "9") (pinfunction "QH*_9") (pintype "tri_state"))
      (node (ref "IC7") (pin "14") (pinfunction "SER_14") (pintype "input"))
    )
    (net (code "69") (name "Net-(IC7A-QA)") (class "Default")
      (node (ref "IC7") (pin "15") (pinfunction "QA_15") (pintype "tri_state"))
      (node (ref "R41") (pin "1") (pinfunction "1_1") (pintype "passive"))
    )
    (net (code "70") (name "Net-(IC7A-QB)") (class "Default")
      (node (ref "IC7") (pin "1") (pinfunction "QB_1") (pintype "tri_state"))
      (node (ref "R42") (pin "1") (pinfunction "1_1") (pintype "passive"))
    )
    (net (code "71") (name "Net-(IC7A-QC)") (class "Default")
      (node (ref "IC7") (pin "2") (pinfunction "QC_2") (pintype "tri_state"))
      (node (ref "R43") (pin "1") (pinfunction "1_1") (pintype "passive"))
    )
    (net (code "72") (name "Net-(IC7A-QD)") (class "Default")
      (node (ref "IC7") (pin "3") (pinfunction "QD_3") (pintype "tri_state"))
      (node (ref "R44") (pin "1") (pinfunction "1_1") (pintype "passive"))
    )
    (net (code "73") (name "Net-(IC7A-QE)") (class "Default")
      (node (ref "IC7") (pin "4") (pinfunction "QE_4") (pintype "tri_state"))
      (node (ref "R45") (pin "1") (pinfunction "1_1") (pintype "passive"))
    )
    (net (code "74") (name "Net-(IC7A-QF)") (class "Default")
      (node (ref "IC7") (pin "5") (pinfunction "QF_5") (pintype "tri_state"))
      (node (ref "R46") (pin "1") (pinfunction "1_1") (pintype "passive"))
    )
    (net (code "75") (name "Net-(IC7A-QG)") (class "Default")
      (node (ref "IC7") (pin "6") (pinfunction "QG_6") (pintype "tri_state"))
      (node (ref "R47") (pin "1") (pinfunction "1_1") (pintype "passive"))
    )
    (net (code "76") (name "Net-(IC7A-QH)") (class "Default")
      (node (ref "IC7") (pin "7") (pinfunction "QH_7") (pintype "tri_state"))
      (node (ref "R48") (pin "1") (pinfunction "1_1") (pintype "passive"))
    )
    (net (code "77") (name "Net-(IC7A-QH*)") (class "Default")
      (node (ref "IC7") (pin "9") (pinfunction "QH*_9") (pintype "tri_state"))
      (node (ref "IC8") (pin "14") (pinfunction "SER_14") (pintype "input"))
    )
    (net (code "78") (name "Net-(IC8A-QA)") (class "Default")
      (node (ref "IC8") (pin "15") (pinfunction "QA_15") (pintype "tri_state"))
      (node (ref "R49") (pin "1") (pinfunction "1_1") (pintype "passive"))
    )
    (net (code "79") (name "Net-(IC8A-QB)") (class "Default")
      (node (ref "IC8") (pin "1") (pinfunction "QB_1") (pintype "tri_state"))
      (node (ref "R50") (pin "1") (pinfunction "1_1") (pintype "passive"))
    )
    (net (code "80") (name "Net-(IC8A-QC)") (class "Default")
      (node (ref "IC8") (pin "2") (pinfunction "QC_2") (pintype "tri_state"))
      (node (ref "R51") (pin "1") (pinfunction "1_1") (pintype "passive"))
    )
    (net (code "81") (name "Net-(IC8A-QD)") (class "Default")
      (node (ref "IC8") (pin "3") (pinfunction "QD_3") (pintype "tri_state"))
      (node (ref "R52") (pin "1") (pinfunction "1_1") (pintype "passive"))
    )
    (net (code "82") (name "Net-(IC8A-QE)") (class "Default")
      (node (ref "IC8") (pin "4") (pinfunction "QE_4") (pintype "tri_state"))
      (node (ref "R53") (pin "1") (pinfunction "1_1") (pintype "passive"))
    )
    (net (code "83") (name "Net-(IC8A-QF)") (class "Default")
      (node (ref "IC8") (pin "5") (pinfunction "QF_5") (pintype "tri_state"))
      (node (ref "R54") (pin "1") (pinfunction "1_1") (pintype "passive"))
    )
    (net (code "84") (name "Net-(IC8A-QG)") (class "Default")
      (node (ref "IC8") (pin "6") (pinfunction "QG_6") (pintype "tri_state"))
      (node (ref "R55") (pin "1") (pinfunction "1_1") (pintype "passive"))
    )
    (net (code "85") (name "Net-(IC8A-QH)") (class "Default")
      (node (ref "IC8") (pin "7") (pinfunction "QH_7") (pintype "tri_state"))
      (node (ref "R56") (pin "1") (pinfunction "1_1") (pintype "passive"))
    )
    (net (code "86") (name "Net-(IC8A-QH*)") (class "Default")
      (node (ref "IC8") (pin "9") (pinfunction "QH*_9") (pintype "tri_state"))
      (node (ref "IC9") (pin "14") (pinfunction "SER_14") (pintype "input"))
    )
    (net (code "87") (name "Net-(IC9A-QA)") (class "Default")
      (node (ref "IC9") (pin "15") (pinfunction "QA_15") (pintype "tri_state"))
      (node (ref "R57") (pin "1") (pinfunction "1_1") (pintype "passive"))
    )
    (net (code "88") (name "Net-(IC9A-QB)") (class "Default")
      (node (ref "IC9") (pin "1") (pinfunction "QB_1") (pintype "tri_state"))
      (node (ref "R58") (pin "1") (pinfunction "1_1") (pintype "passive"))
    )
    (net (code "89") (name "Net-(IC9A-QC)") (class "Default")
      (node (ref "IC9") (pin "2") (pinfunction "QC_2") (pintype "tri_state"))
      (node (ref "R59") (pin "1") (pinfunction "1_1") (pintype "passive"))
    )
    (net (code "90") (name "Net-(IC9A-QD)") (class "Default")
      (node (ref "IC9") (pin "3") (pinfunction "QD_3") (pintype "tri_state"))
      (node (ref "R60") (pin "1") (pinfunction "1_1") (pintype "passive"))
    )
    (net (code "91") (name "Net-(IC9A-QE)") (class "Default")
      (node (ref "IC9") (pin "4") (pinfunction "QE_4") (pintype "tri_state"))
      (node (ref "R61") (pin "1") (pinfunction "1_1") (pintype "passive"))
    )
    (net (code "92") (name "Net-(IC9A-QF)") (class "Default")
      (node (ref "IC9") (pin "5") (pinfunction "QF_5") (pintype "tri_state"))
      (node (ref "R62") (pin "1") (pinfunction "1_1") (pintype "passive"))
    )
    (net (code "93") (name "Net-(IC9A-QG)") (class "Default")
      (node (ref "IC9") (pin "6") (pinfunction "QG_6") (pintype "tri_state"))
      (node (ref "R63") (pin "1") (pinfunction "1_1") (pintype "passive"))
    )
    (net (code "94") (name "Net-(IC9A-QH)") (class "Default")
      (node (ref "IC9") (pin "7") (pinfunction "QH_7") (pintype "tri_state"))
      (node (ref "R64") (pin "1") (pinfunction "1_1") (pintype "passive"))
    )
    (net (code "95") (name "Net-(LED1-PadA)") (class "Default")
      (node (ref "LED1") (pin "A") (pinfunction "A_A") (pintype "passive"))
      (node (ref "R68") (pin "2") (pinfunction "2_2") (pintype "passive"))
    )
    (net (code "96") (name "Net-(LED2-PadA)") (class "Default")
      (node (ref "LED2") (pin "A") (pinfunction "A_A") (pintype "passive"))
      (node (ref "R69") (pin "2") (pinfunction "2_2") (pintype "passive"))
    )
    (net (code "97") (name "Net-(POWER-LED-PadA)") (class "Default")
      (node (ref "POWER-LED") (pin "A") (pinfunction "A_A") (pintype "passive"))
      (node (ref "R70") (pin "2") (pinfunction "2_2") (pintype "passive"))
    )
    (net (code "98") (name "Net-(R1-Pad2)") (class "Default")
      (node (ref "R1") (pin "2") (pinfunction "2_2") (pintype "passive"))
      (node (ref "ROW1") (pin "1") (pinfunction "1_1") (pintype "passive"))
    )
    (net (code "99") (name "Net-(R2-Pad2)") (class "Default")
      (node (ref "R2") (pin "2") (pinfunction "2_2") (pintype "passive"))
      (node (ref "ROW1") (pin "2") (pinfunction "2_2") (pintype "passive"))
    )
    (net (code "100") (name "Net-(R3-Pad2)") (class "Default")
      (node (ref "R3") (pin "2") (pinfunction "2_2") (pintype "passive"))
      (node (ref "ROW1") (pin "3") (pinfunction "3_3") (pintype "passive"))
    )
    (net (code "101") (name "Net-(R4-Pad2)") (class "Default")
      (node (ref "R4") (pin "2") (pinfunction "2_2") (pintype "passive"))
      (node (ref "ROW1") (pin "4") (pinfunction "4_4") (pintype "passive"))
    )
    (net (code "102") (name "Net-(R5-Pad2)") (class "Default")
      (node (ref "R5") (pin "2") (pinfunction "2_2") (pintype "passive"))
      (node (ref "ROW1") (pin "5") (pinfunction "5_5") (pintype "passive"))
    )
    (net (code "103") (name "Net-(R6-Pad2)") (class "Default")
      (node (ref "R6") (pin "2") (pinfunction "2_2") (pintype "passive"))
      (node (ref "ROW1") (pin "6") (pinfunction "6_6") (pintype "passive"))
    )
    (net (code "104") (name "Net-(R7-Pad2)") (class "Default")
      (node (ref "R7") (pin "2") (pinfunction "2_2") (pintype "passive"))
      (node (ref "ROW1") (pin "7") (pinfunction "7_7") (pintype "passive"))
    )
    (net (code "105") (name "Net-(R8-Pad2)") (class "Default")
      (node (ref "R8") (pin "2") (pinfunction "2_2") (pintype "passive"))
      (node (ref "ROW1") (pin "8") (pinfunction "8_8") (pintype "passive"))
    )
    (net (code "106") (name "Net-(R9-Pad2)") (class "Default")
      (node (ref "R9") (pin "2") (pinfunction "2_2") (pintype "passive"))
      (node (ref "ROW2") (pin "1") (pinfunction "1_1") (pintype "passive"))
    )
    (net (code "107") (name "Net-(R10-Pad2)") (class "Default")
      (node (ref "R10") (pin "2") (pinfunction "2_2") (pintype "passive"))
      (node (ref "ROW2") (pin "2") (pinfunction "2_2") (pintype "passive"))
    )
    (net (code "108") (name "Net-(R11-Pad2)") (class "Default")
      (node (ref "R11") (pin "2") (pinfunction "2_2") (pintype "passive"))
      (node (ref "ROW2") (pin "3") (pinfunction "3_3") (pintype "passive"))
    )
    (net (code "109") (name "Net-(R12-Pad2)") (class "Default")
      (node (ref "R12") (pin "2") (pinfunction "2_2") (pintype "passive"))
      (node (ref "ROW2") (pin "4") (pinfunction "4_4") (pintype "passive"))
    )
    (net (code "110") (name "Net-(R13-Pad2)") (class "Default")
      (node (ref "R13") (pin "2") (pinfunction "2_2") (pintype "passive"))
      (node (ref "ROW2") (pin "5") (pinfunction "5_5") (pintype "passive"))
    )
    (net (code "111") (name "Net-(R14-Pad2)") (class "Default")
      (node (ref "R14") (pin "2") (pinfunction "2_2") (pintype "passive"))
      (node (ref "ROW2") (pin "6") (pinfunction "6_6") (pintype "passive"))
    )
    (net (code "112") (name "Net-(R15-Pad2)") (class "Default")
      (node (ref "R15") (pin "2") (pinfunction "2_2") (pintype "passive"))
      (node (ref "ROW2") (pin "7") (pinfunction "7_7") (pintype "passive"))
    )
    (net (code "113") (name "Net-(R16-Pad2)") (class "Default")
      (node (ref "R16") (pin "2") (pinfunction "2_2") (pintype "passive"))
      (node (ref "ROW2") (pin "8") (pinfunction "8_8") (pintype "passive"))
    )
    (net (code "114") (name "Net-(R17-Pad2)") (class "Default")
      (node (ref "R17") (pin "2") (pinfunction "2_2") (pintype "passive"))
      (node (ref "ROW3") (pin "1") (pinfunction "1_1") (pintype "passive"))
    )
    (net (code "115") (name "Net-(R18-Pad2)") (class "Default")
      (node (ref "R18") (pin "2") (pinfunction "2_2") (pintype "passive"))
      (node (ref "ROW3") (pin "2") (pinfunction "2_2") (pintype "passive"))
    )
    (net (code "116") (name "Net-(R19-Pad2)") (class "Default")
      (node (ref "R19") (pin "2") (pinfunction "2_2") (pintype "passive"))
      (node (ref "ROW3") (pin "3") (pinfunction "3_3") (pintype "passive"))
    )
    (net (code "117") (name "Net-(R20-Pad2)") (class "Default")
      (node (ref "R20") (pin "2") (pinfunction "2_2") (pintype "passive"))
      (node (ref "ROW3") (pin "4") (pinfunction "4_4") (pintype "passive"))
    )
    (net (code "118") (name "Net-(R21-Pad2)") (class "Default")
      (node (ref "R21") (pin "2") (pinfunction "2_2") (pintype "passive"))
      (node (ref "ROW3") (pin "5") (pinfunction "5_5") (pintype "passive"))
    )
    (net (code "119") (name "Net-(R22-Pad2)") (class "Default")
      (node (ref "R22") (pin "2") (pinfunction "2_2") (pintype "passive"))
      (node (ref "ROW3") (pin "6") (pinfunction "6_6") (pintype "passive"))
    )
    (net (code "120") (name "Net-(R23-Pad2)") (class "Default")
      (node (ref "R23") (pin "2") (pinfunction "2_2") (pintype "passive"))
      (node (ref "ROW3") (pin "7") (pinfunction "7_7") (pintype "passive"))
    )
    (net (code "121") (name "Net-(R24-Pad2)") (class "Default")
      (node (ref "R24") (pin "2") (pinfunction "2_2") (pintype "passive"))
      (node (ref "ROW3") (pin "8") (pinfunction "8_8") (pintype "passive"))
    )
    (net (code "122") (name "Net-(R25-Pad2)") (class "Default")
      (node (ref "R25") (pin "2") (pinfunction "2_2") (pintype "passive"))
      (node (ref "ROW4") (pin "1") (pinfunction "1_1") (pintype "passive"))
    )
    (net (code "123") (name "Net-(R26-Pad2)") (class "Default")
      (node (ref "R26") (pin "2") (pinfunction "2_2") (pintype "passive"))
      (node (ref "ROW4") (pin "2") (pinfunction "2_2") (pintype "passive"))
    )
    (net (code "124") (name "Net-(R27-Pad2)") (class "Default")
      (node (ref "R27") (pin "2") (pinfunction "2_2") (pintype "passive"))
      (node (ref "ROW4") (pin "3") (pinfunction "3_3") (pintype "passive"))
    )
    (net (code "125") (name "Net-(R28-Pad2)") (class "Default")
      (node (ref "R28") (pin "2") (pinfunction "2_2") (pintype "passive"))
      (node (ref "ROW4") (pin "4") (pinfunction "4_4") (pintype "passive"))
    )
    (net (code "126") (name "Net-(R29-Pad2)") (class "Default")
      (node (ref "R29") (pin "2") (pinfunction "2_2") (pintype "passive"))
      (node (ref "ROW4") (pin "5") (pinfunction "5_5") (pintype "passive"))
    )
    (net (code "127") (name "Net-(R30-Pad2)") (class "Default")
      (node (ref "R30") (pin "2") (pinfunction "2_2") (pintype "passive"))
      (node (ref "ROW4") (pin "6") (pinfunction "6_6") (pintype "passive"))
    )
    (net (code "128") (name "Net-(R31-Pad2)") (class "Default")
      (node (ref "R31") (pin "2") (pinfunction "2_2") (pintype "passive"))
      (node (ref "ROW4") (pin "7") (pinfunction "7_7") (pintype "passive"))
    )
    (net (code "129") (name "Net-(R32-Pad2)") (class "Default")
      (node (ref "R32") (pin "2") (pinfunction "2_2") (pintype "passive"))
      (node (ref "ROW4") (pin "8") (pinfunction "8_8") (pintype "passive"))
    )
    (net (code "130") (name "Net-(R33-Pad2)") (class "Default")
      (node (ref "R33") (pin "2") (pinfunction "2_2") (pintype "passive"))
      (node (ref "ROW5") (pin "1") (pinfunction "1_1") (pintype "passive"))
    )
    (net (code "131") (name "Net-(R34-Pad2)") (class "Default")
      (node (ref "R34") (pin "2") (pinfunction "2_2") (pintype "passive"))
      (node (ref "ROW5") (pin "2") (pinfunction "2_2") (pintype "passive"))
    )
    (net (code "132") (name "Net-(R35-Pad2)") (class "Default")
      (node (ref "R35") (pin "2") (pinfunction "2_2") (pintype "passive"))
      (node (ref "ROW5") (pin "3") (pinfunction "3_3") (pintype "passive"))
    )
    (net (code "133") (name "Net-(R36-Pad2)") (class "Default")
      (node (ref "R36") (pin "2") (pinfunction "2_2") (pintype "passive"))
      (node (ref "ROW5") (pin "4") (pinfunction "4_4") (pintype "passive"))
    )
    (net (code "134") (name "Net-(R37-Pad2)") (class "Default")
      (node (ref "R37") (pin "2") (pinfunction "2_2") (pintype "passive"))
      (node (ref "ROW5") (pin "5") (pinfunction "5_5") (pintype "passive"))
    )
    (net (code "135") (name "Net-(R38-Pad2)") (class "Default")
      (node (ref "R38") (pin "2") (pinfunction "2_2") (pintype "passive"))
      (node (ref "ROW5") (pin "6") (pinfunction "6_6") (pintype "passive"))
    )
    (net (code "136") (name "Net-(R39-Pad2)") (class "Default")
      (node (ref "R39") (pin "2") (pinfunction "2_2") (pintype "passive"))
      (node (ref "ROW5") (pin "7") (pinfunction "7_7") (pintype "passive"))
    )
    (net (code "137") (name "Net-(R40-Pad2)") (class "Default")
      (node (ref "R40") (pin "2") (pinfunction "2_2") (pintype "passive"))
      (node (ref "ROW5") (pin "8") (pinfunction "8_8") (pintype "passive"))
    )
    (net (code "138") (name "Net-(R41-Pad2)") (class "Default")
      (node (ref "R41") (pin "2") (pinfunction "2_2") (pintype "passive"))
      (node (ref "ROW6") (pin "1") (pinfunction "1_1") (pintype "passive"))
    )
    (net (code "139") (name "Net-(R42-Pad2)") (class "Default")
      (node (ref "R42") (pin "2") (pinfunction "2_2") (pintype "passive"))
      (node (ref "ROW6") (pin "2") (pinfunction "2_2") (pintype "passive"))
    )
    (net (code "140") (name "Net-(R43-Pad2)") (class "Default")
      (node (ref "R43") (pin "2") (pinfunction "2_2") (pintype "passive"))
      (node (ref "ROW6") (pin "3") (pinfunction "3_3") (pintype "passive"))
    )
    (net (code "141") (name "Net-(R44-Pad2)") (class "Default")
      (node (ref "R44") (pin "2") (pinfunction "2_2") (pintype "passive"))
      (node (ref "ROW6") (pin "4") (pinfunction "4_4") (pintype "passive"))
    )
    (net (code "142") (name "Net-(R45-Pad2)") (class "Default")
      (node (ref "R45") (pin "2") (pinfunction "2_2") (pintype "passive"))
      (node (ref "ROW6") (pin "5") (pinfunction "5_5") (pintype "passive"))
    )
    (net (code "143") (name "Net-(R46-Pad2)") (class "Default")
      (node (ref "R46") (pin "2") (pinfunction "2_2") (pintype "passive"))
      (node (ref "ROW6") (pin "6") (pinfunction "6_6") (pintype "passive"))
    )
    (net (code "144") (name "Net-(R47-Pad2)") (class "Default")
      (node (ref "R47") (pin "2") (pinfunction "2_2") (pintype "passive"))
      (node (ref "ROW6") (pin "7") (pinfunction "7_7") (pintype "passive"))
    )
    (net (code "145") (name "Net-(R48-Pad2)") (class "Default")
      (node (ref "R48") (pin "2") (pinfunction "2_2") (pintype "passive"))
      (node (ref "ROW6") (pin "8") (pinfunction "8_8") (pintype "passive"))
    )
    (net (code "146") (name "Net-(R49-Pad2)") (class "Default")
      (node (ref "R49") (pin "2") (pinfunction "2_2") (pintype "passive"))
      (node (ref "ROW7") (pin "1") (pinfunction "1_1") (pintype "passive"))
    )
    (net (code "147") (name "Net-(R50-Pad2)") (class "Default")
      (node (ref "R50") (pin "2") (pinfunction "2_2") (pintype "passive"))
      (node (ref "ROW7") (pin "2") (pinfunction "2_2") (pintype "passive"))
    )
    (net (code "148") (name "Net-(R51-Pad2)") (class "Default")
      (node (ref "R51") (pin "2") (pinfunction "2_2") (pintype "passive"))
      (node (ref "ROW7") (pin "3") (pinfunction "3_3") (pintype "passive"))
    )
    (net (code "149") (name "Net-(R52-Pad2)") (class "Default")
      (node (ref "R52") (pin "2") (pinfunction "2_2") (pintype "passive"))
      (node (ref "ROW7") (pin "4") (pinfunction "4_4") (pintype "passive"))
    )
    (net (code "150") (name "Net-(R53-Pad2)") (class "Default")
      (node (ref "R53") (pin "2") (pinfunction "2_2") (pintype "passive"))
      (node (ref "ROW7") (pin "5") (pinfunction "5_5") (pintype "passive"))
    )
    (net (code "151") (name "Net-(R54-Pad2)") (class "Default")
      (node (ref "R54") (pin "2") (pinfunction "2_2") (pintype "passive"))
      (node (ref "ROW7") (pin "6") (pinfunction "6_6") (pintype "passive"))
    )
    (net (code "152") (name "Net-(R55-Pad2)") (class "Default")
      (node (ref "R55") (pin "2") (pinfunction "2_2") (pintype "passive"))
      (node (ref "ROW7") (pin "7") (pinfunction "7_7") (pintype "passive"))
    )
    (net (code "153") (name "Net-(R56-Pad2)") (class "Default")
      (node (ref "R56") (pin "2") (pinfunction "2_2") (pintype "passive"))
      (node (ref "ROW7") (pin "8") (pinfunction "8_8") (pintype "passive"))
    )
    (net (code "154") (name "Net-(R57-Pad2)") (class "Default")
      (node (ref "R57") (pin "2") (pinfunction "2_2") (pintype "passive"))
      (node (ref "ROW8") (pin "1") (pinfunction "1_1") (pintype "passive"))
    )
    (net (code "155") (name "Net-(R58-Pad2)") (class "Default")
      (node (ref "R58") (pin "2") (pinfunction "2_2") (pintype "passive"))
      (node (ref "ROW8") (pin "2") (pinfunction "2_2") (pintype "passive"))
    )
    (net (code "156") (name "Net-(R59-Pad2)") (class "Default")
      (node (ref "R59") (pin "2") (pinfunction "2_2") (pintype "passive"))
      (node (ref "ROW8") (pin "3") (pinfunction "3_3") (pintype "passive"))
    )
    (net (code "157") (name "Net-(R60-Pad2)") (class "Default")
      (node (ref "R60") (pin "2") (pinfunction "2_2") (pintype "passive"))
      (node (ref "ROW8") (pin "4") (pinfunction "4_4") (pintype "passive"))
    )
    (net (code "158") (name "Net-(R61-Pad2)") (class "Default")
      (node (ref "R61") (pin "2") (pinfunction "2_2") (pintype "passive"))
      (node (ref "ROW8") (pin "5") (pinfunction "5_5") (pintype "passive"))
    )
    (net (code "159") (name "Net-(R62-Pad2)") (class "Default")
      (node (ref "R62") (pin "2") (pinfunction "2_2") (pintype "passive"))
      (node (ref "ROW8") (pin "6") (pinfunction "6_6") (pintype "passive"))
    )
    (net (code "160") (name "Net-(R63-Pad2)") (class "Default")
      (node (ref "R63") (pin "2") (pinfunction "2_2") (pintype "passive"))
      (node (ref "ROW8") (pin "7") (pinfunction "7_7") (pintype "passive"))
    )
    (net (code "161") (name "Net-(R64-Pad2)") (class "Default")
      (node (ref "R64") (pin "2") (pinfunction "2_2") (pintype "passive"))
      (node (ref "ROW8") (pin "8") (pinfunction "8_8") (pintype "passive"))
    )
    (net (code "162") (name "Net-(U$1-D)") (class "Default")
      (node (ref "LAYERS") (pin "7") (pinfunction "7_7") (pintype "passive"))
      (node (ref "U$1") (pin "3") (pinfunction "D_3") (pintype "passive"))
    )
    (net (code "163") (name "Net-(U$2-D)") (class "Default")
      (node (ref "LAYERS") (pin "5") (pinfunction "5_5") (pintype "passive"))
      (node (ref "U$2") (pin "3") (pinfunction "D_3") (pintype "passive"))
    )
    (net (code "164") (name "Net-(U$3-D)") (class "Default")
      (node (ref "LAYERS") (pin "4") (pinfunction "4_4") (pintype "passive"))
      (node (ref "U$3") (pin "3") (pinfunction "D_3") (pintype "passive"))
    )
    (net (code "165") (name "Net-(U$4-D)") (class "Default")
      (node (ref "LAYERS") (pin "8") (pinfunction "8_8") (pintype "passive"))
      (node (ref "U$4") (pin "3") (pinfunction "D_3") (pintype "passive"))
    )
    (net (code "166") (name "Net-(U$5-D)") (class "Default")
      (node (ref "LAYERS") (pin "6") (pinfunction "6_6") (pintype "passive"))
      (node (ref "U$5") (pin "3") (pinfunction "D_3") (pintype "passive"))
    )
    (net (code "167") (name "Net-(U$6-D)") (class "Default")
      (node (ref "LAYERS") (pin "3") (pinfunction "3_3") (pintype "passive"))
      (node (ref "U$6") (pin "3") (pinfunction "D_3") (pintype "passive"))
    )
    (net (code "168") (name "Net-(U$7-D)") (class "Default")
      (node (ref "LAYERS") (pin "1") (pinfunction "1_1") (pintype "passive"))
      (node (ref "U$7") (pin "3") (pinfunction "D_3") (pintype "passive"))
    )
    (net (code "169") (name "Net-(U$8-D)") (class "Default")
      (node (ref "LAYERS") (pin "2") (pinfunction "2_2") (pintype "passive"))
      (node (ref "U$8") (pin "3") (pinfunction "D_3") (pintype "passive"))
    )
    (net (code "170") (name "unconnected-(IC1-(ADC0)PA0-Pad37)") (class "Default")
      (node (ref "IC1") (pin "37") (pinfunction "(ADC0)PA0_37") (pintype "bidirectional"))
    )
    (net (code "171") (name "unconnected-(IC1-(ADC1)PA1-Pad36)") (class "Default")
      (node (ref "IC1") (pin "36") (pinfunction "(ADC1)PA1_36") (pintype "bidirectional"))
    )
    (net (code "172") (name "unconnected-(IC1-(ADC2)PA2-Pad35)") (class "Default")
      (node (ref "IC1") (pin "35") (pinfunction "(ADC2)PA2_35") (pintype "bidirectional"))
    )
    (net (code "173") (name "unconnected-(IC1-(ADC3)PA3-Pad34)") (class "Default")
      (node (ref "IC1") (pin "34") (pinfunction "(ADC3)PA3_34") (pintype "bidirectional"))
    )
    (net (code "174") (name "unconnected-(IC1-(ADC4)PA4-Pad33)") (class "Default")
      (node (ref "IC1") (pin "33") (pinfunction "(ADC4)PA4_33") (pintype "bidirectional"))
    )
    (net (code "175") (name "unconnected-(IC1-(ADC5)PA5-Pad32)") (class "Default")
      (node (ref "IC1") (pin "32") (pinfunction "(ADC5)PA5_32") (pintype "bidirectional"))
    )
    (net (code "176") (name "unconnected-(IC1-(ADC6)PA6-Pad31)") (class "Default")
      (node (ref "IC1") (pin "31") (pinfunction "(ADC6)PA6_31") (pintype "bidirectional"))
    )
    (net (code "177") (name "unconnected-(IC1-(ADC7)PA7-Pad30)") (class "Default")
      (node (ref "IC1") (pin "30") (pinfunction "(ADC7)PA7_30") (pintype "bidirectional"))
    )
    (net (code "178") (name "unconnected-(IC1-(AIN0{slash}INT2)PB2-Pad42)") (class "Default")
      (node (ref "IC1") (pin "42") (pinfunction "(AIN0/INT2)PB2_42") (pintype "bidirectional"))
    )
    (net (code "179") (name "unconnected-(IC1-(AIN1{slash}OC0)PB3-Pad43)") (class "Default")
      (node (ref "IC1") (pin "43") (pinfunction "(AIN1/OC0)PB3_43") (pintype "bidirectional"))
    )
    (net (code "180") (name "unconnected-(IC1-(ICP)PD6-Pad15)") (class "Default")
      (node (ref "IC1") (pin "15") (pinfunction "(ICP)PD6_15") (pintype "bidirectional"))
    )
    (net (code "181") (name "unconnected-(IC1-(OC1A)PD5-Pad14)") (class "Default")
      (node (ref "IC1") (pin "14") (pinfunction "(OC1A)PD5_14") (pintype "bidirectional"))
    )
    (net (code "182") (name "unconnected-(IC1-(OC1B)PD4-Pad13)") (class "Default")
      (node (ref "IC1") (pin "13") (pinfunction "(OC1B)PD4_13") (pintype "bidirectional"))
    )
    (net (code "183") (name "unconnected-(IC1-(OC2)PD7-Pad16)") (class "Default")
      (node (ref "IC1") (pin "16") (pinfunction "(OC2)PD7_16") (pintype "bidirectional"))
    )
    (net (code "184") (name "unconnected-(IC1-(T0{slash}XCK)PB0-Pad40)") (class "Default")
      (node (ref "IC1") (pin "40") (pinfunction "(T0/XCK)PB0_40") (pintype "bidirectional"))
    )
    (net (code "185") (name "unconnected-(IC1-(T1)PB1-Pad41)") (class "Default")
      (node (ref "IC1") (pin "41") (pinfunction "(T1)PB1_41") (pintype "bidirectional"))
    )
    (net (code "186") (name "unconnected-(IC9A-QH*-Pad9)") (class "Default")
      (node (ref "IC9") (pin "9") (pinfunction "QH*_9") (pintype "tri_state"))
    )
    (net (code "187") (name "unconnected-(S1-2.2-Pad4)") (class "Default")
      (node (ref "S1") (pin "4") (pinfunction "2.2_4") (pintype "passive"))
    )
  )
)
